# YellowMotorEncoder.net
KiCad netlist of a schematic drawn in EAGLE
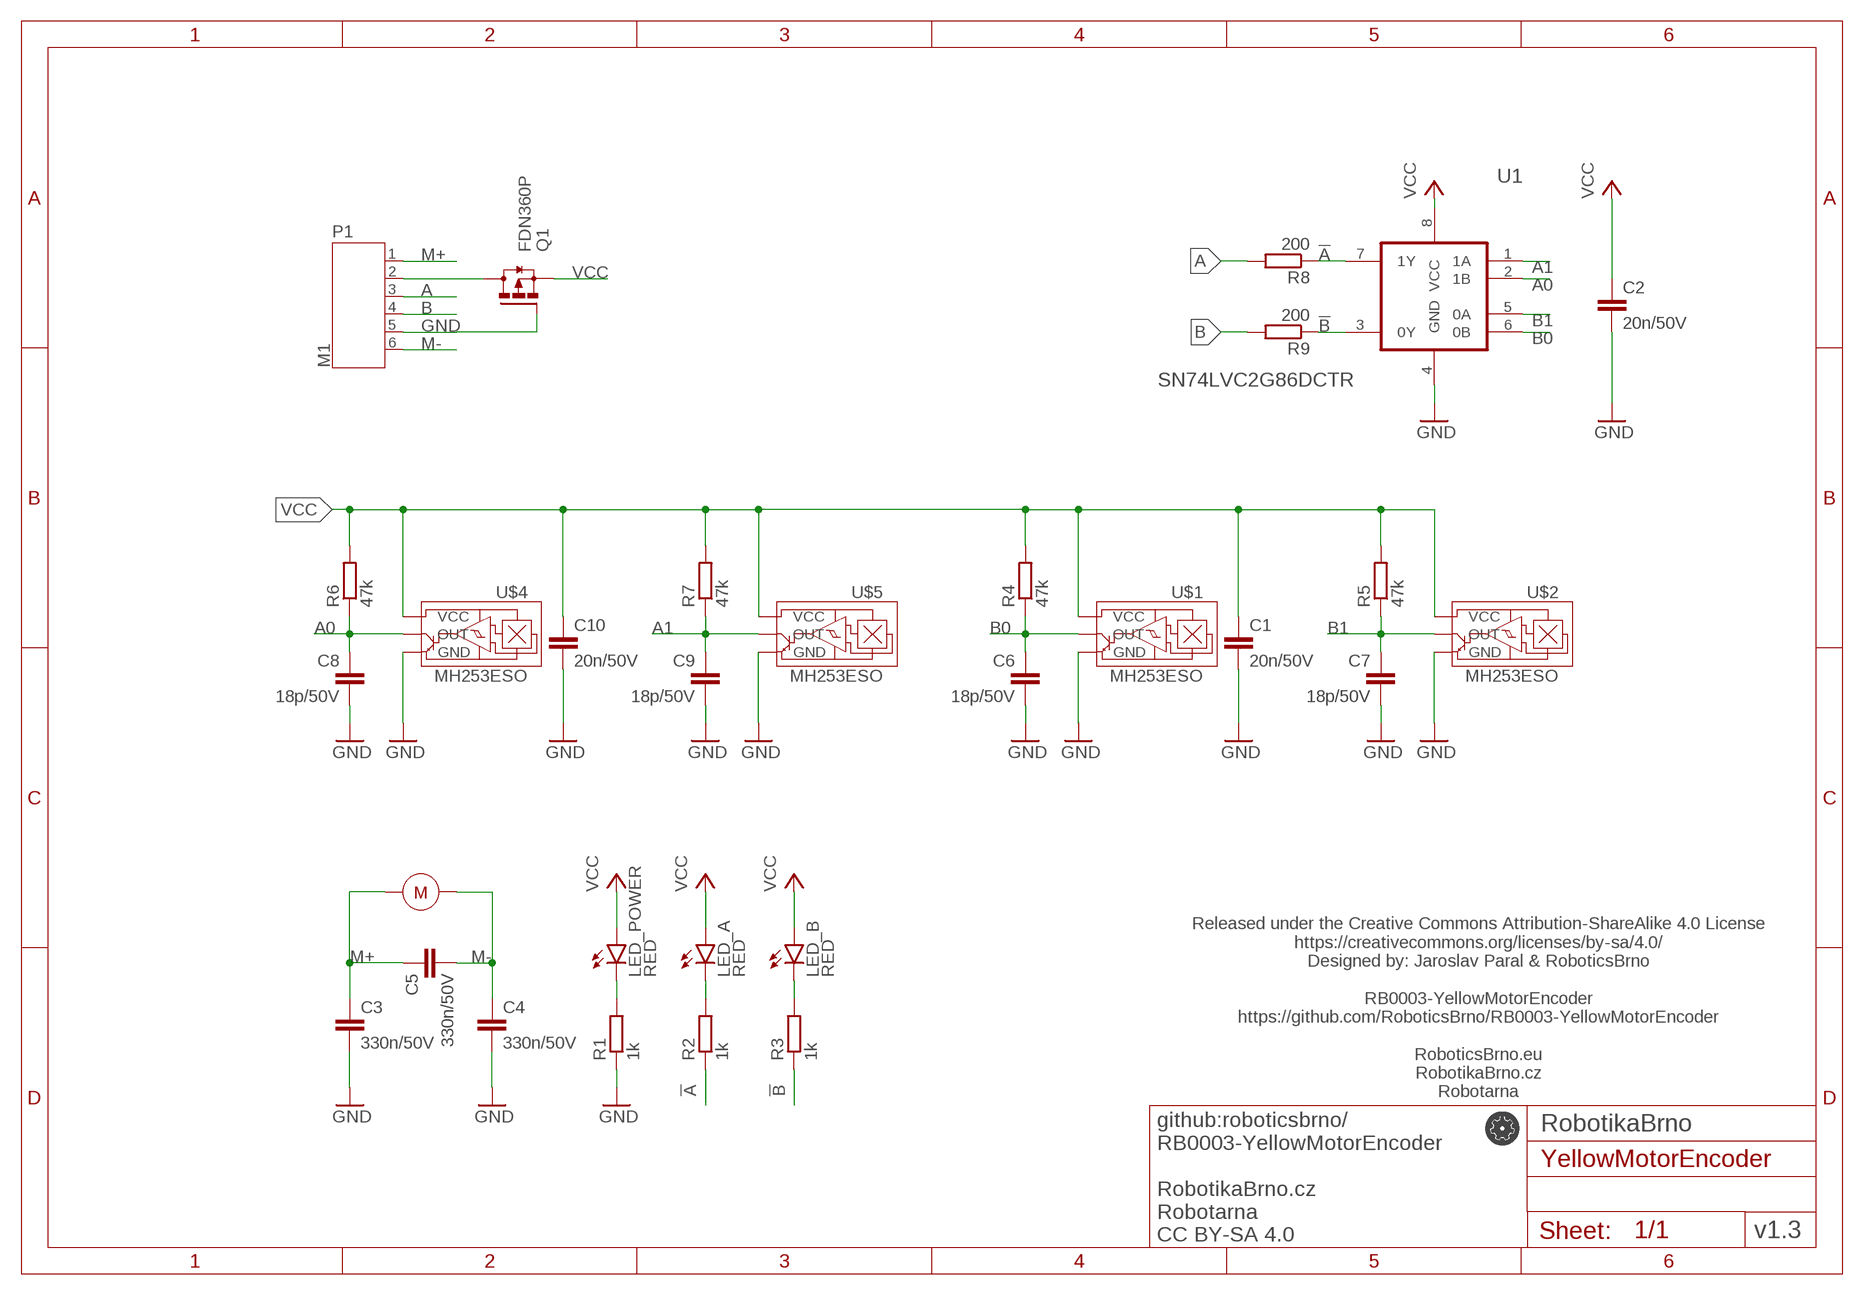
[diagram p0: schematic, sheet 1]

(export (version "E")
  (design (tool "Eeschema 10.0.6"))
  (components
    (comp (ref "C1")
      (value "20n/50V")
      (footprint "eagle-import:C0402")
      (description "MULTILAYER CERAMIC CAPACITORS MLCC - SMD/SMT 10NF 50V 0402 ROHS")
      (fields (field (name "MF") "Samsung Electro-Mechanics"))
      (libsource (lib "eagle-import") (part "rcl_upravena_C-EUC0402"))
    )
    (comp (ref "C2")
      (value "20n/50V")
      (footprint "eagle-import:C0402")
      (description "MULTILAYER CERAMIC CAPACITORS MLCC - SMD/SMT 10NF 50V 0402 ROHS")
      (fields (field (name "MF") "Samsung Electro-Mechanics"))
      (libsource (lib "eagle-import") (part "rcl_upravena_C-EUC0402"))
    )
    (comp (ref "C3")
      (value "330n/50V")
      (footprint "eagle-import:C0805")
      (description "MULTILAYER CERAMIC CAPACITORS MLCC - SMD/SMT 330NF 50V 0805 ROHS")
      (fields (field (name "MF") "Guangdong Fenghua Advanced Tech"))
      (libsource (lib "eagle-import") (part "C-EUC0805"))
    )
    (comp (ref "C4")
      (value "330n/50V")
      (footprint "eagle-import:C0805")
      (description "MULTILAYER CERAMIC CAPACITORS MLCC - SMD/SMT 330NF 50V 0805 ROHS")
      (fields (field (name "MF") "Guangdong Fenghua Advanced Tech"))
      (libsource (lib "eagle-import") (part "C-EUC0805"))
    )
    (comp (ref "C5")
      (value "330n/50V")
      (footprint "eagle-import:C0805")
      (description "MULTILAYER CERAMIC CAPACITORS MLCC - SMD/SMT 330NF 50V 0805 ROHS")
      (fields (field (name "MF") "Guangdong Fenghua Advanced Tech"))
      (libsource (lib "eagle-import") (part "C-EUC0805"))
    )
    (comp (ref "C6")
      (value "18p/50V")
      (footprint "eagle-import:C0402")
      (description "MULTILAYER CERAMIC CAPACITORS MLCC - SMD/SMT 18PF 50V 0402 ROHS")
      (fields (field (name "MF") "Guangdong Fenghua Advanced Tech"))
      (libsource (lib "eagle-import") (part "rcl_upravena_C-EUC0402"))
    )
    (comp (ref "C7")
      (value "18p/50V")
      (footprint "eagle-import:C0402")
      (description "MULTILAYER CERAMIC CAPACITORS MLCC - SMD/SMT 18PF 50V 0402 ROHS")
      (fields (field (name "MF") "Guangdong Fenghua Advanced Tech"))
      (libsource (lib "eagle-import") (part "rcl_upravena_C-EUC0402"))
    )
    (comp (ref "C8")
      (value "18p/50V")
      (footprint "eagle-import:C0402")
      (description "MULTILAYER CERAMIC CAPACITORS MLCC - SMD/SMT 18PF 50V 0402 ROHS")
      (fields (field (name "MF") "Guangdong Fenghua Advanced Tech"))
      (libsource (lib "eagle-import") (part "rcl_upravena_C-EUC0402"))
    )
    (comp (ref "C9")
      (value "18p/50V")
      (footprint "eagle-import:C0402")
      (description "MULTILAYER CERAMIC CAPACITORS MLCC - SMD/SMT 18PF 50V 0402 ROHS")
      (fields (field (name "MF") "Guangdong Fenghua Advanced Tech"))
      (libsource (lib "eagle-import") (part "rcl_upravena_C-EUC0402"))
    )
    (comp (ref "C10")
      (value "20n/50V")
      (footprint "eagle-import:C0402")
      (description "MULTILAYER CERAMIC CAPACITORS MLCC - SMD/SMT 10NF 50V 0402 ROHS")
      (fields (field (name "MF") "Samsung Electro-Mechanics"))
      (libsource (lib "eagle-import") (part "rcl_upravena_C-EUC0402"))
    )
    (comp (ref "LED_A")
      (value "RED")
      (footprint "eagle-import:CHIPLED_0603")
      (description "LIGHT EMITTING DIODES (LED) RED 520~625NM 90~100MCD@20MA TOP VIEW 0603 ROHS")
      (fields (field (name "MF") "Hubei KENTO Elec"))
      (libsource (lib "eagle-import") (part "LEDCHIPLED_0603"))
    )
    (comp (ref "LED_B")
      (value "RED")
      (footprint "eagle-import:CHIPLED_0603")
      (description "LIGHT EMITTING DIODES (LED) RED 520~625NM 90~100MCD@20MA TOP VIEW 0603 ROHS")
      (fields (field (name "MF") "Hubei KENTO Elec"))
      (libsource (lib "eagle-import") (part "LEDCHIPLED_0603"))
    )
    (comp (ref "LED_POWER")
      (value "RED")
      (footprint "eagle-import:CHIPLED_0603")
      (description "LIGHT EMITTING DIODES (LED) RED 520~625NM 90~100MCD@20MA TOP VIEW 0603 ROHS")
      (fields (field (name "MF") "Hubei KENTO Elec"))
      (libsource (lib "eagle-import") (part "LEDCHIPLED_0603"))
    )
    (comp (ref "M1")
      (value "YELLOW_MOTORV2")
      (footprint "eagle-import:YELLOW_MOTOR_V2")
      (libsource (lib "eagle-import") (part "YELLOW_MOTORV2"))
    )
    (comp (ref "P1")
      (value "M1")
      (footprint "eagle-import:JST-PH6")
      (libsource (lib "eagle-import") (part "JST-PH6"))
    )
    (comp (ref "Q1")
      (value "FDN360P")
      (footprint "eagle-import:SUPER-SOT3")
      (libsource (lib "eagle-import") (part "FDN360P"))
    )
    (comp (ref "R1")
      (value "1k")
      (footprint "eagle-import:R0402")
      (description "CHIP RESISTOR - SURFACE MOUNT 1KOHMS ±1% 1/10W 0603 ROHS")
      (fields (field (name "MF") "Uniroyal Elec"))
      (libsource (lib "eagle-import") (part "R-EU_R0402"))
    )
    (comp (ref "R2")
      (value "1k")
      (footprint "eagle-import:R0402")
      (description "CHIP RESISTOR - SURFACE MOUNT 1KOHMS ±1% 1/10W 0603 ROHS")
      (fields (field (name "MF") "Uniroyal Elec"))
      (libsource (lib "eagle-import") (part "R-EU_R0402"))
    )
    (comp (ref "R3")
      (value "1k")
      (footprint "eagle-import:R0402")
      (description "CHIP RESISTOR - SURFACE MOUNT 1KOHMS ±1% 1/10W 0603 ROHS")
      (fields (field (name "MF") "Uniroyal Elec"))
      (libsource (lib "eagle-import") (part "R-EU_R0402"))
    )
    (comp (ref "R4")
      (value "47k")
      (footprint "eagle-import:R0402")
      (description "CHIP RESISTOR - SURFACE MOUNT 47KOHMS ±1% 1/10W 0603 ROHS")
      (fields (field (name "MF") "Uniroyal Elec"))
      (libsource (lib "eagle-import") (part "R-EU_R0402"))
    )
    (comp (ref "R5")
      (value "47k")
      (footprint "eagle-import:R0402")
      (description "CHIP RESISTOR - SURFACE MOUNT 47KOHMS ±1% 1/10W 0603 ROHS")
      (fields (field (name "MF") "Uniroyal Elec"))
      (libsource (lib "eagle-import") (part "R-EU_R0402"))
    )
    (comp (ref "R6")
      (value "47k")
      (footprint "eagle-import:R0402")
      (description "CHIP RESISTOR - SURFACE MOUNT 47KOHMS ±1% 1/10W 0603 ROHS")
      (fields (field (name "MF") "Uniroyal Elec"))
      (libsource (lib "eagle-import") (part "R-EU_R0402"))
    )
    (comp (ref "R7")
      (value "47k")
      (footprint "eagle-import:R0402")
      (description "CHIP RESISTOR - SURFACE MOUNT 47KOHMS ±1% 1/10W 0603 ROHS")
      (fields (field (name "MF") "Uniroyal Elec"))
      (libsource (lib "eagle-import") (part "R-EU_R0402"))
    )
    (comp (ref "R8")
      (value "200")
      (footprint "eagle-import:R0402")
      (description "CHIP RESISTOR - SURFACE MOUNT 47KOHMS ±1% 1/10W 0603 ROHS")
      (fields (field (name "MF") "Uniroyal Elec"))
      (libsource (lib "eagle-import") (part "R-EU_R0402"))
    )
    (comp (ref "R9")
      (value "200")
      (footprint "eagle-import:R0402")
      (description "CHIP RESISTOR - SURFACE MOUNT 47KOHMS ±1% 1/10W 0603 ROHS")
      (fields (field (name "MF") "Uniroyal Elec"))
      (libsource (lib "eagle-import") (part "R-EU_R0402"))
    )
    (comp (ref "U$1")
      (value "MH253ESO")
      (footprint "eagle-import:SOT23")
      (fields (field (name "MF") "Magnesensor Tech (MST)"))
      (libsource (lib "eagle-import") (part "MH253ESO"))
    )
    (comp (ref "U$2")
      (value "MH253ESO")
      (footprint "eagle-import:SOT23")
      (fields (field (name "MF") "Magnesensor Tech (MST)"))
      (libsource (lib "eagle-import") (part "MH253ESO"))
    )
    (comp (ref "U$4")
      (value "MH253ESO")
      (footprint "eagle-import:SOT23")
      (fields (field (name "MF") "Magnesensor Tech (MST)"))
      (libsource (lib "eagle-import") (part "MH253ESO"))
    )
    (comp (ref "U$5")
      (value "MH253ESO")
      (footprint "eagle-import:SOT23")
      (fields (field (name "MF") "Magnesensor Tech (MST)"))
      (libsource (lib "eagle-import") (part "MH253ESO"))
    )
    (comp (ref "U1")
      (value "SN74LVC2G86DCTR")
      (footprint "eagle-import:SOP65P400X130-8N")
      (fields (field (name "MF") "Texas Instruments"))
      (libsource (lib "eagle-import") (part "SN74LVC2G86DCTR"))
    )
  )
  (nets
    (net (code "1") (name "/A0") (class "Default")
      (node (ref "C8") (pin "1") (pinfunction "1_1") (pintype "passive"))
      (node (ref "R6") (pin "1") (pinfunction "1_1") (pintype "passive"))
      (node (ref "U$4") (pin "2") (pinfunction "OUT_2") (pintype "open_collector"))
      (node (ref "U1") (pin "2") (pinfunction "1B_2") (pintype "bidirectional"))
    )
    (net (code "2") (name "/A1") (class "Default")
      (node (ref "C9") (pin "1") (pinfunction "1_1") (pintype "passive"))
      (node (ref "R7") (pin "1") (pinfunction "1_1") (pintype "passive"))
      (node (ref "U$5") (pin "2") (pinfunction "OUT_2") (pintype "open_collector"))
      (node (ref "U1") (pin "1") (pinfunction "1A_1") (pintype "bidirectional"))
    )
    (net (code "3") (name "/B0") (class "Default")
      (node (ref "C6") (pin "1") (pinfunction "1_1") (pintype "passive"))
      (node (ref "R4") (pin "1") (pinfunction "1_1") (pintype "passive"))
      (node (ref "U$1") (pin "2") (pinfunction "OUT_2") (pintype "open_collector"))
      (node (ref "U1") (pin "6") (pinfunction "0B_6") (pintype "bidirectional"))
    )
    (net (code "4") (name "/B1") (class "Default")
      (node (ref "C7") (pin "1") (pinfunction "1_1") (pintype "passive"))
      (node (ref "R5") (pin "1") (pinfunction "1_1") (pintype "passive"))
      (node (ref "U$2") (pin "2") (pinfunction "OUT_2") (pintype "open_collector"))
      (node (ref "U1") (pin "5") (pinfunction "0A_5") (pintype "bidirectional"))
    )
    (net (code "5") (name "/M+") (class "Default")
      (node (ref "C3") (pin "1") (pinfunction "1_1") (pintype "passive"))
      (node (ref "C5") (pin "1") (pinfunction "1_1") (pintype "passive"))
      (node (ref "M1") (pin "P$1") (pinfunction "P$1_P$1") (pintype "passive"))
      (node (ref "P1") (pin "1") (pinfunction "1_1") (pintype "passive"))
    )
    (net (code "6") (name "/M-") (class "Default")
      (node (ref "C4") (pin "1") (pinfunction "1_1") (pintype "passive"))
      (node (ref "C5") (pin "2") (pinfunction "2_2") (pintype "passive"))
      (node (ref "M1") (pin "P$2") (pinfunction "P$2_P$2") (pintype "passive"))
      (node (ref "P1") (pin "6") (pinfunction "6_6") (pintype "passive"))
    )
    (net (code "7") (name "/~{A}") (class "Default")
      (node (ref "R2") (pin "1") (pinfunction "1_1") (pintype "passive"))
      (node (ref "R8") (pin "1") (pinfunction "1_1") (pintype "passive"))
      (node (ref "U1") (pin "7") (pinfunction "1Y_7") (pintype "bidirectional"))
    )
    (net (code "8") (name "/~{B}") (class "Default")
      (node (ref "R3") (pin "1") (pinfunction "1_1") (pintype "passive"))
      (node (ref "R9") (pin "1") (pinfunction "1_1") (pintype "passive"))
      (node (ref "U1") (pin "3") (pinfunction "0Y_3") (pintype "bidirectional"))
    )
    (net (code "9") (name "A") (class "Default")
      (node (ref "P1") (pin "3") (pinfunction "3_3") (pintype "passive"))
      (node (ref "R8") (pin "2") (pinfunction "2_2") (pintype "passive"))
    )
    (net (code "10") (name "B") (class "Default")
      (node (ref "P1") (pin "4") (pinfunction "4_4") (pintype "passive"))
      (node (ref "R9") (pin "2") (pinfunction "2_2") (pintype "passive"))
    )
    (net (code "11") (name "GND") (class "Default")
      (node (ref "C1") (pin "2") (pinfunction "2_2") (pintype "passive"))
      (node (ref "C10") (pin "2") (pinfunction "2_2") (pintype "passive"))
      (node (ref "C2") (pin "2") (pinfunction "2_2") (pintype "passive"))
      (node (ref "C3") (pin "2") (pinfunction "2_2") (pintype "passive"))
      (node (ref "C4") (pin "2") (pinfunction "2_2") (pintype "passive"))
      (node (ref "C6") (pin "2") (pinfunction "2_2") (pintype "passive"))
      (node (ref "C7") (pin "2") (pinfunction "2_2") (pintype "passive"))
      (node (ref "C8") (pin "2") (pinfunction "2_2") (pintype "passive"))
      (node (ref "C9") (pin "2") (pinfunction "2_2") (pintype "passive"))
      (node (ref "P1") (pin "5") (pinfunction "5_5") (pintype "passive"))
      (node (ref "Q1") (pin "1") (pinfunction "G_1") (pintype "passive"))
      (node (ref "R1") (pin "1") (pinfunction "1_1") (pintype "passive"))
      (node (ref "U$1") (pin "3") (pinfunction "GND_3") (pintype "power_in"))
      (node (ref "U$2") (pin "3") (pinfunction "GND_3") (pintype "power_in"))
      (node (ref "U$4") (pin "3") (pinfunction "GND_3") (pintype "power_in"))
      (node (ref "U$5") (pin "3") (pinfunction "GND_3") (pintype "power_in"))
      (node (ref "U1") (pin "4") (pinfunction "GND_4") (pintype "power_in"))
    )
    (net (code "12") (name "Net-(LED_A-PadC)") (class "Default")
      (node (ref "LED_A") (pin "C") (pinfunction "C_C") (pintype "passive"))
      (node (ref "R2") (pin "2") (pinfunction "2_2") (pintype "passive"))
    )
    (net (code "13") (name "Net-(LED_B-PadC)") (class "Default")
      (node (ref "LED_B") (pin "C") (pinfunction "C_C") (pintype "passive"))
      (node (ref "R3") (pin "2") (pinfunction "2_2") (pintype "passive"))
    )
    (net (code "14") (name "Net-(LED_POWER-PadC)") (class "Default")
      (node (ref "LED_POWER") (pin "C") (pinfunction "C_C") (pintype "passive"))
      (node (ref "R1") (pin "2") (pinfunction "2_2") (pintype "passive"))
    )
    (net (code "15") (name "Net-(Q1-D)") (class "Default")
      (node (ref "P1") (pin "2") (pinfunction "2_2") (pintype "passive"))
      (node (ref "Q1") (pin "3") (pinfunction "D_3") (pintype "passive"))
    )
    (net (code "16") (name "VCC") (class "Default")
      (node (ref "C1") (pin "1") (pinfunction "1_1") (pintype "passive"))
      (node (ref "C10") (pin "1") (pinfunction "1_1") (pintype "passive"))
      (node (ref "C2") (pin "1") (pinfunction "1_1") (pintype "passive"))
      (node (ref "LED_A") (pin "A") (pinfunction "A_A") (pintype "passive"))
      (node (ref "LED_B") (pin "A") (pinfunction "A_A") (pintype "passive"))
      (node (ref "LED_POWER") (pin "A") (pinfunction "A_A") (pintype "passive"))
      (node (ref "Q1") (pin "2") (pinfunction "S_2") (pintype "passive"))
      (node (ref "R4") (pin "2") (pinfunction "2_2") (pintype "passive"))
      (node (ref "R5") (pin "2") (pinfunction "2_2") (pintype "passive"))
      (node (ref "R6") (pin "2") (pinfunction "2_2") (pintype "passive"))
      (node (ref "R7") (pin "2") (pinfunction "2_2") (pintype "passive"))
      (node (ref "U$1") (pin "1") (pinfunction "VCC_1") (pintype "power_in"))
      (node (ref "U$2") (pin "1") (pinfunction "VCC_1") (pintype "power_in"))
      (node (ref "U$4") (pin "1") (pinfunction "VCC_1") (pintype "power_in"))
      (node (ref "U$5") (pin "1") (pinfunction "VCC_1") (pintype "power_in"))
      (node (ref "U1") (pin "8") (pinfunction "VCC_8") (pintype "power_in"))
    )
  )
)
